# ATX_Power_Breakout_v1p3.net
KiCad netlist of a schematic drawn in EAGLE
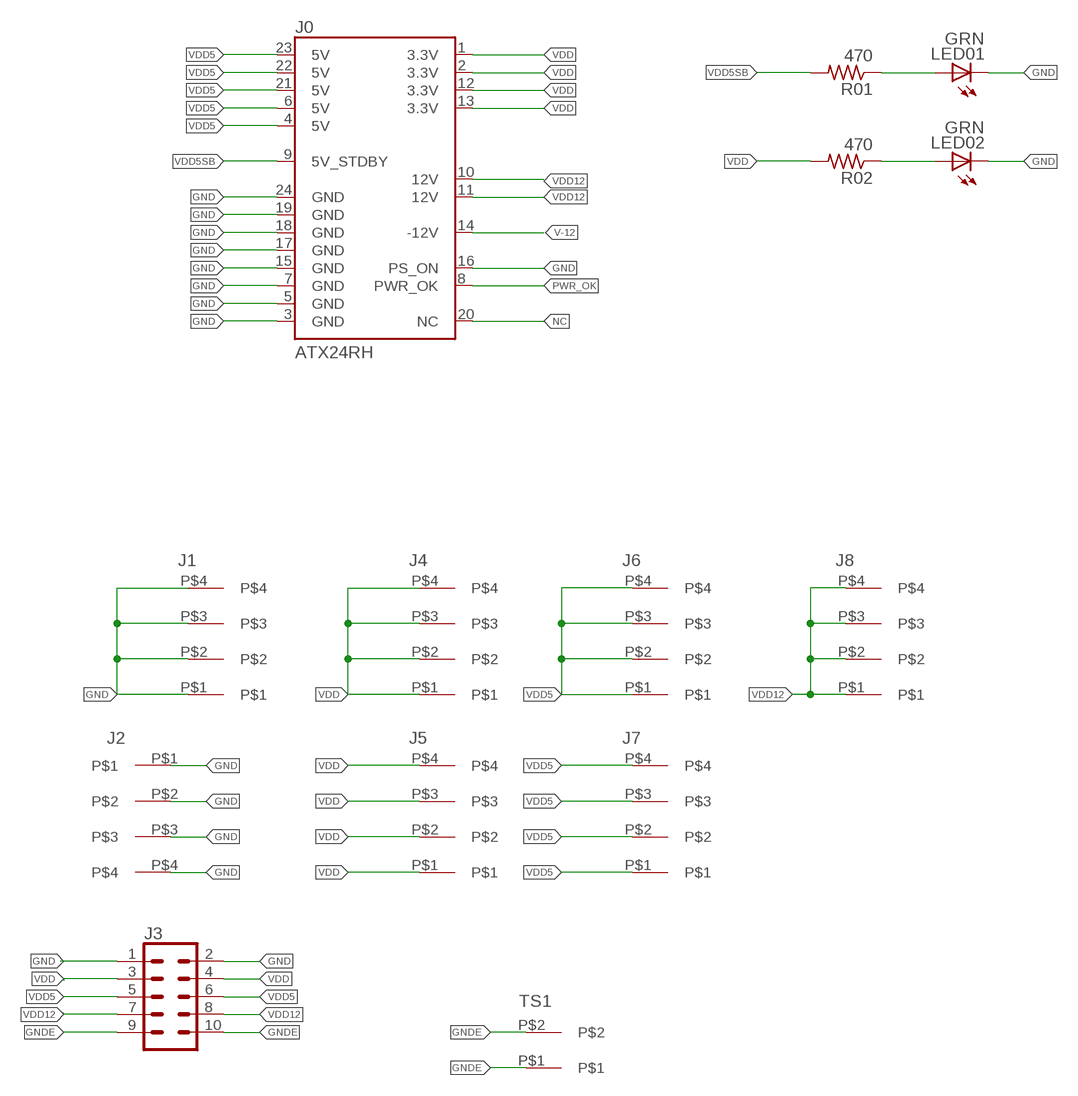
[diagram p0: schematic, sheet 1]

(export (version "E")
  (design (tool "Eeschema 10.0.6"))
  (components
    (comp (ref "J0")
      (value "ATX24RH")
      (footprint "eagle-import:ATX24_RIGHT_ANGLE")
      (libsource (lib "eagle-import") (part "ATX24RH"))
    )
    (comp (ref "J1")
      (value "3.81MM_1_X_4_RT_ANGLE_PLUG_HEADER")
      (footprint "eagle-import:1X4_3.81MM_PITCH")
      (libsource (lib "eagle-import") (part "3.81MM_1_X_4_RT_ANGLE_PLUG_HEADER"))
    )
    (comp (ref "J2")
      (value "3.81MM_1_X_4_RT_ANGLE_PLUG_HEADER")
      (footprint "eagle-import:1X4_3.81MM_PITCH")
      (libsource (lib "eagle-import") (part "3.81MM_1_X_4_RT_ANGLE_PLUG_HEADER"))
    )
    (comp (ref "J3")
      (value "CONN_05X2PTH")
      (footprint "eagle-import:2X5")
      (libsource (lib "eagle-import") (part "CONN_05X2PTH"))
    )
    (comp (ref "J4")
      (value "3.81MM_1_X_4_RT_ANGLE_PLUG_HEADER")
      (footprint "eagle-import:1X4_3.81MM_PITCH")
      (libsource (lib "eagle-import") (part "3.81MM_1_X_4_RT_ANGLE_PLUG_HEADER"))
    )
    (comp (ref "J5")
      (value "3.81MM_1_X_4_RT_ANGLE_PLUG_HEADER")
      (footprint "eagle-import:1X4_3.81MM_PITCH")
      (libsource (lib "eagle-import") (part "3.81MM_1_X_4_RT_ANGLE_PLUG_HEADER"))
    )
    (comp (ref "J6")
      (value "3.81MM_1_X_4_RT_ANGLE_PLUG_HEADER")
      (footprint "eagle-import:1X4_3.81MM_PITCH")
      (libsource (lib "eagle-import") (part "3.81MM_1_X_4_RT_ANGLE_PLUG_HEADER"))
    )
    (comp (ref "J7")
      (value "3.81MM_1_X_4_RT_ANGLE_PLUG_HEADER")
      (footprint "eagle-import:1X4_3.81MM_PITCH")
      (libsource (lib "eagle-import") (part "3.81MM_1_X_4_RT_ANGLE_PLUG_HEADER"))
    )
    (comp (ref "J8")
      (value "3.81MM_1_X_4_RT_ANGLE_PLUG_HEADER")
      (footprint "eagle-import:1X4_3.81MM_PITCH")
      (libsource (lib "eagle-import") (part "3.81MM_1_X_4_RT_ANGLE_PLUG_HEADER"))
    )
    (comp (ref "LED01")
      (value "GREEN")
      (footprint "eagle-import:LED_0805_GREEN")
      (libsource (lib "eagle-import") (part "LED_0805_GREEN"))
    )
    (comp (ref "LED02")
      (value "GREEN")
      (footprint "eagle-import:LED_0805_GREEN")
      (libsource (lib "eagle-import") (part "LED_0805_GREEN"))
    )
    (comp (ref "R01")
      (value "470")
      (footprint "eagle-import:0402")
      (libsource (lib "eagle-import") (part "R_0402"))
    )
    (comp (ref "R02")
      (value "470")
      (footprint "eagle-import:0402")
      (libsource (lib "eagle-import") (part "R_0402"))
    )
    (comp (ref "TS1")
      (value "3.81MM_1_X_2_RT_ANGLE_PLUG_HEADER")
      (footprint "eagle-import:1X2_3.81MM_PITCH")
      (libsource (lib "eagle-import") (part "3.81MM_1_X_2_RT_ANGLE_PLUG_HEADER"))
    )
  )
  (nets
    (net (code "1") (name "GND") (class "Default")
      (node (ref "J0") (pin "15") (pinfunction "GND_15") (pintype "bidirectional"))
      (node (ref "J0") (pin "16") (pinfunction "PS_ON_16") (pintype "bidirectional"))
      (node (ref "J0") (pin "17") (pinfunction "GND_17") (pintype "bidirectional"))
      (node (ref "J0") (pin "18") (pinfunction "GND_18") (pintype "bidirectional"))
      (node (ref "J0") (pin "19") (pinfunction "GND_19") (pintype "bidirectional"))
      (node (ref "J0") (pin "24") (pinfunction "GND_24") (pintype "bidirectional"))
      (node (ref "J0") (pin "3") (pinfunction "GND_3") (pintype "bidirectional"))
      (node (ref "J0") (pin "5") (pinfunction "GND_5") (pintype "bidirectional"))
      (node (ref "J0") (pin "7") (pinfunction "GND_7") (pintype "bidirectional"))
      (node (ref "J1") (pin "P$1") (pinfunction "P$1_P$1") (pintype "bidirectional"))
      (node (ref "J1") (pin "P$2") (pinfunction "P$2_P$2") (pintype "bidirectional"))
      (node (ref "J1") (pin "P$3") (pinfunction "P$3_P$3") (pintype "bidirectional"))
      (node (ref "J1") (pin "P$4") (pinfunction "P$4_P$4") (pintype "bidirectional"))
      (node (ref "J2") (pin "P$1") (pinfunction "P$1_P$1") (pintype "bidirectional"))
      (node (ref "J2") (pin "P$2") (pinfunction "P$2_P$2") (pintype "bidirectional"))
      (node (ref "J2") (pin "P$3") (pinfunction "P$3_P$3") (pintype "bidirectional"))
      (node (ref "J2") (pin "P$4") (pinfunction "P$4_P$4") (pintype "bidirectional"))
      (node (ref "J3") (pin "1") (pinfunction "1_1") (pintype "passive"))
      (node (ref "J3") (pin "2") (pinfunction "2_2") (pintype "passive"))
      (node (ref "LED01") (pin "C") (pinfunction "C_C") (pintype "passive"))
      (node (ref "LED02") (pin "C") (pinfunction "C_C") (pintype "passive"))
    )
    (net (code "2") (name "GNDE") (class "Default")
      (node (ref "J3") (pin "10") (pinfunction "10_10") (pintype "passive"))
      (node (ref "J3") (pin "9") (pinfunction "9_9") (pintype "passive"))
      (node (ref "TS1") (pin "P$1") (pinfunction "P$1_P$1") (pintype "bidirectional"))
      (node (ref "TS1") (pin "P$2") (pinfunction "P$2_P$2") (pintype "bidirectional"))
    )
    (net (code "3") (name "NC") (class "Default")
      (node (ref "J0") (pin "20") (pinfunction "NC_20") (pintype "bidirectional"))
    )
    (net (code "4") (name "Net-(R01-1)") (class "Default")
      (node (ref "LED01") (pin "A") (pinfunction "A_A") (pintype "passive"))
      (node (ref "R01") (pin "P$1") (pinfunction "1_P$1") (pintype "passive"))
    )
    (net (code "5") (name "Net-(R02-1)") (class "Default")
      (node (ref "LED02") (pin "A") (pinfunction "A_A") (pintype "passive"))
      (node (ref "R02") (pin "P$1") (pinfunction "1_P$1") (pintype "passive"))
    )
    (net (code "6") (name "PWR_OK") (class "Default")
      (node (ref "J0") (pin "8") (pinfunction "PWR_OK_8") (pintype "bidirectional"))
    )
    (net (code "7") (name "V-12") (class "Default")
      (node (ref "J0") (pin "14") (pinfunction "-12V_14") (pintype "bidirectional"))
    )
    (net (code "8") (name "VDD") (class "Default")
      (node (ref "J0") (pin "1") (pinfunction "3.3V_1") (pintype "bidirectional"))
      (node (ref "J0") (pin "12") (pinfunction "3.3V_12") (pintype "bidirectional"))
      (node (ref "J0") (pin "13") (pinfunction "3.3V_13") (pintype "bidirectional"))
      (node (ref "J0") (pin "2") (pinfunction "3.3V_2") (pintype "bidirectional"))
      (node (ref "J3") (pin "3") (pinfunction "3_3") (pintype "passive"))
      (node (ref "J3") (pin "4") (pinfunction "4_4") (pintype "passive"))
      (node (ref "J4") (pin "P$1") (pinfunction "P$1_P$1") (pintype "bidirectional"))
      (node (ref "J4") (pin "P$2") (pinfunction "P$2_P$2") (pintype "bidirectional"))
      (node (ref "J4") (pin "P$3") (pinfunction "P$3_P$3") (pintype "bidirectional"))
      (node (ref "J4") (pin "P$4") (pinfunction "P$4_P$4") (pintype "bidirectional"))
      (node (ref "J5") (pin "P$1") (pinfunction "P$1_P$1") (pintype "bidirectional"))
      (node (ref "J5") (pin "P$2") (pinfunction "P$2_P$2") (pintype "bidirectional"))
      (node (ref "J5") (pin "P$3") (pinfunction "P$3_P$3") (pintype "bidirectional"))
      (node (ref "J5") (pin "P$4") (pinfunction "P$4_P$4") (pintype "bidirectional"))
      (node (ref "R02") (pin "P$2") (pinfunction "2_P$2") (pintype "passive"))
    )
    (net (code "9") (name "VDD5") (class "Default")
      (node (ref "J0") (pin "21") (pinfunction "5V_21") (pintype "bidirectional"))
      (node (ref "J0") (pin "22") (pinfunction "5V_22") (pintype "bidirectional"))
      (node (ref "J0") (pin "23") (pinfunction "5V_23") (pintype "bidirectional"))
      (node (ref "J0") (pin "4") (pinfunction "5V_4") (pintype "bidirectional"))
      (node (ref "J0") (pin "6") (pinfunction "5V_6") (pintype "bidirectional"))
      (node (ref "J3") (pin "5") (pinfunction "5_5") (pintype "passive"))
      (node (ref "J3") (pin "6") (pinfunction "6_6") (pintype "passive"))
      (node (ref "J6") (pin "P$1") (pinfunction "P$1_P$1") (pintype "bidirectional"))
      (node (ref "J6") (pin "P$2") (pinfunction "P$2_P$2") (pintype "bidirectional"))
      (node (ref "J6") (pin "P$3") (pinfunction "P$3_P$3") (pintype "bidirectional"))
      (node (ref "J6") (pin "P$4") (pinfunction "P$4_P$4") (pintype "bidirectional"))
      (node (ref "J7") (pin "P$1") (pinfunction "P$1_P$1") (pintype "bidirectional"))
      (node (ref "J7") (pin "P$2") (pinfunction "P$2_P$2") (pintype "bidirectional"))
      (node (ref "J7") (pin "P$3") (pinfunction "P$3_P$3") (pintype "bidirectional"))
      (node (ref "J7") (pin "P$4") (pinfunction "P$4_P$4") (pintype "bidirectional"))
    )
    (net (code "10") (name "VDD5SB") (class "Default")
      (node (ref "J0") (pin "9") (pinfunction "5V_STDBY_9") (pintype "bidirectional"))
      (node (ref "R01") (pin "P$2") (pinfunction "2_P$2") (pintype "passive"))
    )
    (net (code "11") (name "VDD12") (class "Default")
      (node (ref "J0") (pin "10") (pinfunction "12V_10") (pintype "bidirectional"))
      (node (ref "J0") (pin "11") (pinfunction "12V_11") (pintype "bidirectional"))
      (node (ref "J3") (pin "7") (pinfunction "7_7") (pintype "passive"))
      (node (ref "J3") (pin "8") (pinfunction "8_8") (pintype "passive"))
      (node (ref "J8") (pin "P$1") (pinfunction "P$1_P$1") (pintype "bidirectional"))
      (node (ref "J8") (pin "P$2") (pinfunction "P$2_P$2") (pintype "bidirectional"))
      (node (ref "J8") (pin "P$3") (pinfunction "P$3_P$3") (pintype "bidirectional"))
      (node (ref "J8") (pin "P$4") (pinfunction "P$4_P$4") (pintype "bidirectional"))
    )
  )
)
